# CON_USER_20WBOXHDRRAMx2.net
KiCad netlist of a schematic drawn in Altium Designer
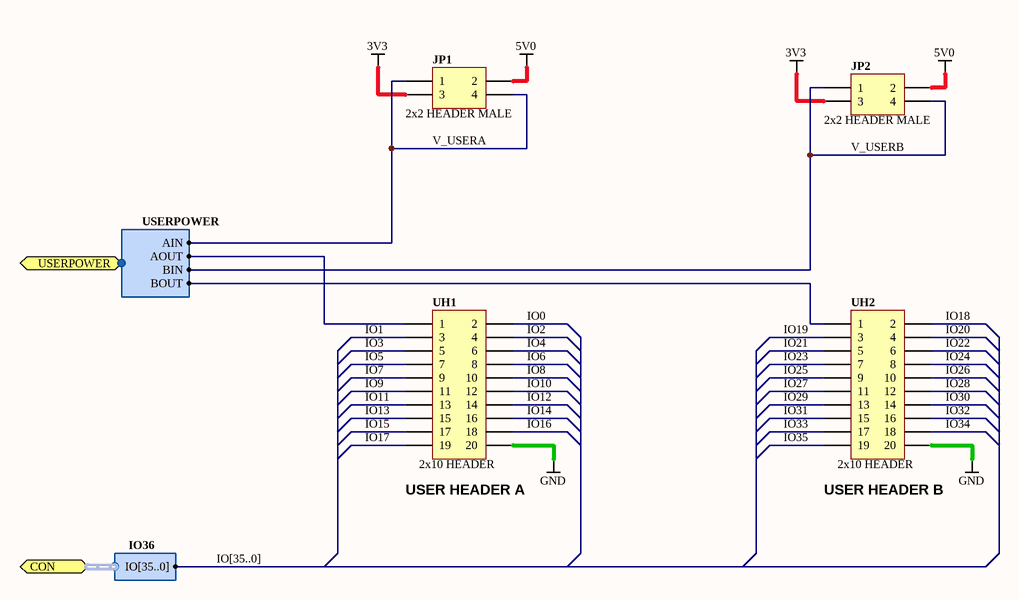
[diagram p0: CON_USER_20WBOXHDRRAMx2.SCHDOC]

(export (version "E")
  (design (tool "Eeschema 10.0.6"))
  (components
    (comp (ref "JP1")
      (value "2x2 HEADER MALE")
      (footprint "HDR2X2")
      (description "Header IDC, 2 x 2 Pin Vertical 2.54mm Pitch (Non-Boxed, Male)")
      (libsource (lib "altium-import") (part "root_0_CON-HDR-2x2-STR_"))
    )
    (comp (ref "JP2")
      (value "2x2 HEADER MALE")
      (footprint "HDR2X2")
      (description "Header IDC, 2 x 2 Pin Vertical 2.54mm Pitch (Non-Boxed, Male)")
      (libsource (lib "altium-import") (part "root_0_CON-HDR-2x2-STR_"))
    )
    (comp (ref "UH1")
      (value "2x10 HEADER")
      (footprint "HDR2X10")
      (description "Header IDC, 2 x 10 Pin Vertical 2.54mm Pitch (Non-Boxed, Male)")
      (libsource (lib "altium-import") (part "root_0_CON-HDR-2x10-STR_"))
    )
    (comp (ref "UH2")
      (value "2x10 HEADER")
      (footprint "HDR2X10")
      (description "Header IDC, 2 x 10 Pin Vertical 2.54mm Pitch (Non-Boxed, Male)")
      (libsource (lib "altium-import") (part "root_0_CON-HDR-2x10-STR_"))
    )
  )
  (nets
    (net (code "3") (name "/AOUT") (class "Default")
      (node (ref "UH1") (pin "1") (pinfunction "1_1") (pintype "passive"))
    )
    (net (code "4") (name "/BOUT") (class "Default")
      (node (ref "UH2") (pin "1") (pinfunction "1_1") (pintype "passive"))
    )
    (net (code "6") (name "/IO0") (class "Default")
      (node (ref "UH1") (pin "2") (pinfunction "2_2") (pintype "passive"))
    )
    (net (code "7") (name "/IO1") (class "Default")
      (node (ref "UH1") (pin "3") (pinfunction "3_3") (pintype "passive"))
    )
    (net (code "8") (name "/IO2") (class "Default")
      (node (ref "UH1") (pin "4") (pinfunction "4_4") (pintype "passive"))
    )
    (net (code "9") (name "/IO3") (class "Default")
      (node (ref "UH1") (pin "5") (pinfunction "5_5") (pintype "passive"))
    )
    (net (code "10") (name "/IO4") (class "Default")
      (node (ref "UH1") (pin "6") (pinfunction "6_6") (pintype "passive"))
    )
    (net (code "11") (name "/IO5") (class "Default")
      (node (ref "UH1") (pin "7") (pinfunction "7_7") (pintype "passive"))
    )
    (net (code "12") (name "/IO6") (class "Default")
      (node (ref "UH1") (pin "8") (pinfunction "8_8") (pintype "passive"))
    )
    (net (code "13") (name "/IO7") (class "Default")
      (node (ref "UH1") (pin "9") (pinfunction "9_9") (pintype "passive"))
    )
    (net (code "14") (name "/IO8") (class "Default")
      (node (ref "UH1") (pin "10") (pinfunction "10_10") (pintype "passive"))
    )
    (net (code "15") (name "/IO9") (class "Default")
      (node (ref "UH1") (pin "11") (pinfunction "11_11") (pintype "passive"))
    )
    (net (code "16") (name "/IO10") (class "Default")
      (node (ref "UH1") (pin "12") (pinfunction "12_12") (pintype "passive"))
    )
    (net (code "17") (name "/IO11") (class "Default")
      (node (ref "UH1") (pin "13") (pinfunction "13_13") (pintype "passive"))
    )
    (net (code "18") (name "/IO12") (class "Default")
      (node (ref "UH1") (pin "14") (pinfunction "14_14") (pintype "passive"))
    )
    (net (code "19") (name "/IO13") (class "Default")
      (node (ref "UH1") (pin "15") (pinfunction "15_15") (pintype "passive"))
    )
    (net (code "20") (name "/IO14") (class "Default")
      (node (ref "UH1") (pin "16") (pinfunction "16_16") (pintype "passive"))
    )
    (net (code "21") (name "/IO15") (class "Default")
      (node (ref "UH1") (pin "17") (pinfunction "17_17") (pintype "passive"))
    )
    (net (code "22") (name "/IO16") (class "Default")
      (node (ref "UH1") (pin "18") (pinfunction "18_18") (pintype "passive"))
    )
    (net (code "23") (name "/IO17") (class "Default")
      (node (ref "UH1") (pin "19") (pinfunction "19_19") (pintype "passive"))
    )
    (net (code "24") (name "/IO18") (class "Default")
      (node (ref "UH2") (pin "2") (pinfunction "2_2") (pintype "passive"))
    )
    (net (code "25") (name "/IO19") (class "Default")
      (node (ref "UH2") (pin "3") (pinfunction "3_3") (pintype "passive"))
    )
    (net (code "26") (name "/IO20") (class "Default")
      (node (ref "UH2") (pin "4") (pinfunction "4_4") (pintype "passive"))
    )
    (net (code "27") (name "/IO21") (class "Default")
      (node (ref "UH2") (pin "5") (pinfunction "5_5") (pintype "passive"))
    )
    (net (code "28") (name "/IO22") (class "Default")
      (node (ref "UH2") (pin "6") (pinfunction "6_6") (pintype "passive"))
    )
    (net (code "29") (name "/IO23") (class "Default")
      (node (ref "UH2") (pin "7") (pinfunction "7_7") (pintype "passive"))
    )
    (net (code "30") (name "/IO24") (class "Default")
      (node (ref "UH2") (pin "8") (pinfunction "8_8") (pintype "passive"))
    )
    (net (code "31") (name "/IO25") (class "Default")
      (node (ref "UH2") (pin "9") (pinfunction "9_9") (pintype "passive"))
    )
    (net (code "32") (name "/IO26") (class "Default")
      (node (ref "UH2") (pin "10") (pinfunction "10_10") (pintype "passive"))
    )
    (net (code "33") (name "/IO27") (class "Default")
      (node (ref "UH2") (pin "11") (pinfunction "11_11") (pintype "passive"))
    )
    (net (code "34") (name "/IO28") (class "Default")
      (node (ref "UH2") (pin "12") (pinfunction "12_12") (pintype "passive"))
    )
    (net (code "35") (name "/IO29") (class "Default")
      (node (ref "UH2") (pin "13") (pinfunction "13_13") (pintype "passive"))
    )
    (net (code "36") (name "/IO30") (class "Default")
      (node (ref "UH2") (pin "14") (pinfunction "14_14") (pintype "passive"))
    )
    (net (code "37") (name "/IO31") (class "Default")
      (node (ref "UH2") (pin "15") (pinfunction "15_15") (pintype "passive"))
    )
    (net (code "38") (name "/IO32") (class "Default")
      (node (ref "UH2") (pin "16") (pinfunction "16_16") (pintype "passive"))
    )
    (net (code "39") (name "/IO33") (class "Default")
      (node (ref "UH2") (pin "17") (pinfunction "17_17") (pintype "passive"))
    )
    (net (code "40") (name "/IO34") (class "Default")
      (node (ref "UH2") (pin "18") (pinfunction "18_18") (pintype "passive"))
    )
    (net (code "41") (name "/IO35") (class "Default")
      (node (ref "UH2") (pin "19") (pinfunction "19_19") (pintype "passive"))
    )
    (net (code "42") (name "/V_USERA") (class "Default")
      (node (ref "JP1") (pin "1") (pinfunction "1_1") (pintype "passive"))
      (node (ref "JP1") (pin "4") (pinfunction "4_4") (pintype "passive"))
    )
    (net (code "43") (name "/V_USERB") (class "Default")
      (node (ref "JP2") (pin "1") (pinfunction "1_1") (pintype "passive"))
      (node (ref "JP2") (pin "4") (pinfunction "4_4") (pintype "passive"))
    )
    (net (code "46") (name "3V3") (class "Default")
      (node (ref "JP1") (pin "3") (pinfunction "3_3") (pintype "passive"))
      (node (ref "JP2") (pin "3") (pinfunction "3_3") (pintype "passive"))
    )
    (net (code "47") (name "5V0") (class "Default")
      (node (ref "JP1") (pin "2") (pinfunction "2_2") (pintype "passive"))
      (node (ref "JP2") (pin "2") (pinfunction "2_2") (pintype "passive"))
    )
    (net (code "48") (name "GND") (class "Default")
      (node (ref "UH1") (pin "20") (pinfunction "20_20") (pintype "passive"))
      (node (ref "UH2") (pin "20") (pinfunction "20_20") (pintype "passive"))
    )
  )
)
